# MY_FOC_2.net
KiCad netlist of a schematic drawn in Altium Designer
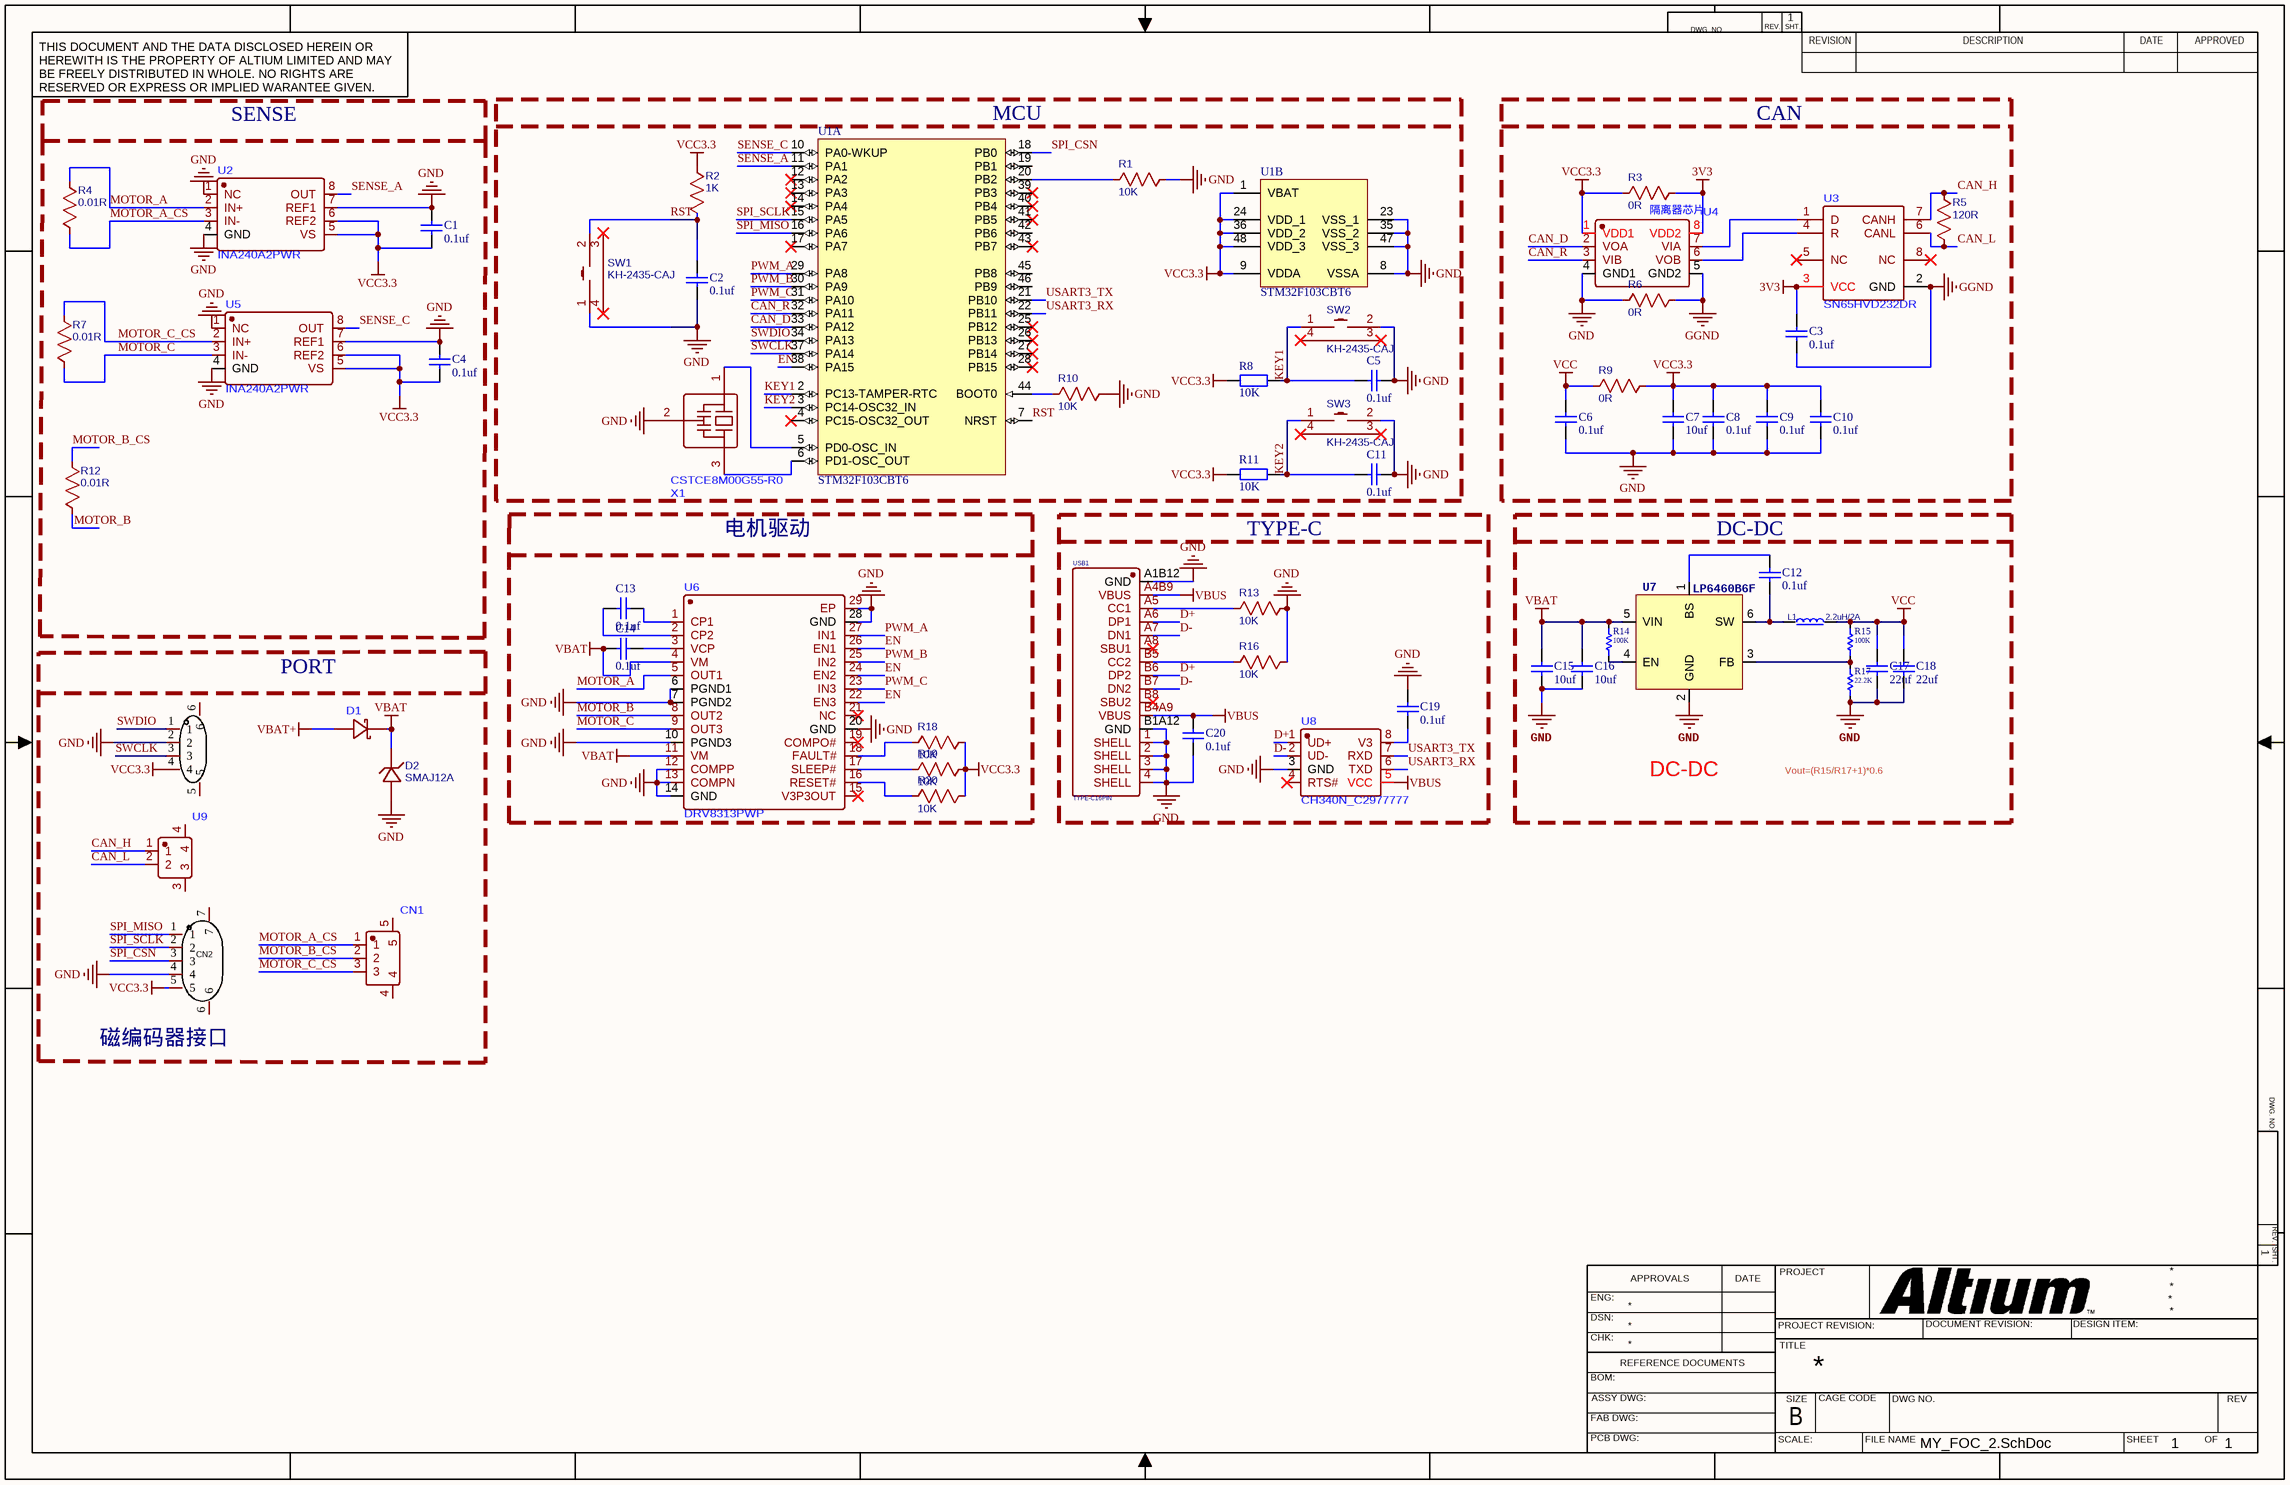
[diagram p0: MY_FOC_2.SchDoc]

(export (version "E")
  (design (tool "Eeschema 10.0.6"))
  (components
    (comp (ref "C1")
      (value "0.1uf")
      (footprint "CAP_0402")
      (description "Capacitor")
      (fields (field (name "Comment") "Cap") (field (name "PUBLISHER") "Altium Limited"))
      (libsource (lib "simple_foc") (part "Cap"))
    )
    (comp (ref "C2")
      (value "0.1uf")
      (footprint "CAP_0402")
      (description "Capacitor")
      (fields (field (name "Comment") "Cap") (field (name "PUBLISHER") "Altium Limited"))
      (libsource (lib "simple_foc") (part "Cap"))
    )
    (comp (ref "C3")
      (value "0.1uf")
      (footprint "CAP_0402")
      (description "Capacitor")
      (fields (field (name "Comment") "Cap") (field (name "PUBLISHER") "Altium Limited"))
      (libsource (lib "simple_foc") (part "Cap"))
    )
    (comp (ref "C4")
      (value "0.1uf")
      (footprint "CAP_0402")
      (description "Capacitor")
      (fields (field (name "Comment") "Cap") (field (name "PUBLISHER") "Altium Limited"))
      (libsource (lib "simple_foc") (part "Cap"))
    )
    (comp (ref "C5")
      (value "0.1uf")
      (footprint "CAP_0402")
      (description "Capacitor")
      (fields (field (name "Comment") "Cap") (field (name "PUBLISHER") "Altium Limited"))
      (libsource (lib "simple_foc") (part "Cap"))
    )
    (comp (ref "C6")
      (value "0.1uf")
      (footprint "CAP_0402")
      (description "Capacitor")
      (fields (field (name "Comment") "Cap") (field (name "PUBLISHER") "Altium Limited"))
      (libsource (lib "simple_foc") (part "Cap"))
    )
    (comp (ref "C7")
      (value "10uf")
      (footprint "CAP_0402")
      (description "Capacitor")
      (fields (field (name "Comment") "Cap") (field (name "PUBLISHER") "Altium Limited"))
      (libsource (lib "simple_foc") (part "Cap"))
    )
    (comp (ref "C8")
      (value "0.1uf")
      (footprint "CAP_0402")
      (description "Capacitor")
      (fields (field (name "Comment") "Cap") (field (name "PUBLISHER") "Altium Limited"))
      (libsource (lib "simple_foc") (part "Cap"))
    )
    (comp (ref "C9")
      (value "0.1uf")
      (footprint "CAP_0402")
      (description "Capacitor")
      (fields (field (name "Comment") "Cap") (field (name "PUBLISHER") "Altium Limited"))
      (libsource (lib "simple_foc") (part "Cap"))
    )
    (comp (ref "C10")
      (value "0.1uf")
      (footprint "CAP_0402")
      (description "Capacitor")
      (fields (field (name "Comment") "Cap") (field (name "PUBLISHER") "Altium Limited"))
      (libsource (lib "simple_foc") (part "Cap"))
    )
    (comp (ref "C11")
      (value "0.1uf")
      (footprint "CAP_0402")
      (description "Capacitor")
      (fields (field (name "Comment") "Cap") (field (name "PUBLISHER") "Altium Limited"))
      (libsource (lib "simple_foc") (part "Cap"))
    )
    (comp (ref "C12")
      (value "0.1uf")
      (footprint "CAP_0402")
      (description "Capacitor")
      (fields (field (name "Comment") "Cap") (field (name "PUBLISHER") "Altium Limited"))
      (libsource (lib "simple_foc") (part "Cap"))
    )
    (comp (ref "C13")
      (value "0.1uf")
      (footprint "CAP_0402")
      (description "Capacitor")
      (fields (field (name "Comment") "Cap") (field (name "PUBLISHER") "Altium Limited"))
      (libsource (lib "simple_foc") (part "Cap"))
    )
    (comp (ref "C14")
      (value "0.1uf")
      (footprint "CAP_0402")
      (description "Capacitor")
      (fields (field (name "Comment") "Cap") (field (name "PUBLISHER") "Altium Limited"))
      (libsource (lib "simple_foc") (part "Cap"))
    )
    (comp (ref "C15")
      (value "10uf")
      (footprint "CAP_0402")
      (description "Capacitor")
      (fields (field (name "Comment") "Cap") (field (name "PUBLISHER") "Altium Limited"))
      (libsource (lib "simple_foc") (part "Cap"))
    )
    (comp (ref "C16")
      (value "10uf")
      (footprint "CAP_0402")
      (description "Capacitor")
      (fields (field (name "Comment") "Cap") (field (name "PUBLISHER") "Altium Limited"))
      (libsource (lib "simple_foc") (part "Cap"))
    )
    (comp (ref "C17")
      (value "22uf")
      (footprint "CAP_0402")
      (description "Capacitor")
      (fields (field (name "Comment") "Cap") (field (name "PUBLISHER") "Altium Limited"))
      (libsource (lib "simple_foc") (part "Cap"))
    )
    (comp (ref "C18")
      (value "22uf")
      (footprint "CAP_0402")
      (description "Capacitor")
      (fields (field (name "Comment") "Cap") (field (name "PUBLISHER") "Altium Limited"))
      (libsource (lib "simple_foc") (part "Cap"))
    )
    (comp (ref "C19")
      (value "0.1uf")
      (footprint "CAP_0402")
      (description "Capacitor")
      (fields (field (name "Comment") "Cap") (field (name "PUBLISHER") "Altium Limited"))
      (libsource (lib "simple_foc") (part "Cap"))
    )
    (comp (ref "C20")
      (value "0.1uf")
      (footprint "CAP_0402")
      (description "Capacitor")
      (fields (field (name "Comment") "Cap") (field (name "PUBLISHER") "Altium Limited"))
      (libsource (lib "simple_foc") (part "Cap"))
    )
    (comp (ref "CN1")
      (value "~")
      (footprint "SH1.0-3P-L")
      (libsource (lib "altium-import") (part "root_0_SH1.0-3P-L_"))
    )
    (comp (ref "CN2")
      (value "HDGC1002WR-S-5P")
      (footprint "SH1.0-5P-L")
      (fields (field (name "MANUFACTURER") "HDGC(华德共创)"))
      (libsource (lib "altium-import") (part "root_0_HDGC1002WR-S-5P_"))
    )
    (comp (ref "CN3")
      (value "HDGC1002WR-S-4P")
      (footprint "SH1.0-4P-L")
      (fields (field (name "MANUFACTURER") "HDGC(华德共创)"))
      (libsource (lib "altium-import") (part "root_0_HDGC1002WR-S-4P_"))
    )
    (comp (ref "D1")
      (value "~")
      (footprint "DO-214AC - duplicate")
      (libsource (lib "altium-import") (part "root_2_SS54A_"))
    )
    (comp (ref "D2")
      (value "SMAJ12A")
      (footprint "SMA_L4.4-W2.8-LS5.4-RD")
      (fields
        (field (name "BOM_SUPPLIER PART") "C309908")
        (field (name "BOM_MANUFACTURER PART") "SMAJ70A")
        (field (name "CONTRIBUTOR") "LCSC")
      )
      (libsource (lib "Schlib1") (part "SMAJ12A"))
    )
    (comp (ref "L1")
      (value "2.2uH/2A")
      (footprint "Inductor_CD_43")
      (description "贴片电感")
      (libsource (lib "*") (part "PL4020"))
    )
    (comp (ref "R1")
      (value "10K")
      (footprint "RES_0402")
      (fields (field (name "CONTRIBUTOR") "LCEDA_Lib"))
      (libsource (lib "simple_foc") (part "0R"))
    )
    (comp (ref "R2")
      (value "1K")
      (footprint "RES_0402")
      (fields (field (name "CONTRIBUTOR") "LCEDA_Lib"))
      (libsource (lib "simple_foc") (part "0R"))
    )
    (comp (ref "R3")
      (value "0R")
      (footprint "RES_0402")
      (fields (field (name "CONTRIBUTOR") "LCEDA_Lib"))
      (libsource (lib "simple_foc") (part "0R"))
    )
    (comp (ref "R4")
      (value "0.01R")
      (footprint "R1206")
      (fields (field (name "CONTRIBUTOR") "LCEDA_Lib"))
      (libsource (lib "simple_foc") (part "0R"))
    )
    (comp (ref "R5")
      (value "120R")
      (footprint "RES_0402")
      (fields (field (name "CONTRIBUTOR") "LCEDA_Lib"))
      (libsource (lib "simple_foc") (part "0R"))
    )
    (comp (ref "R6")
      (value "0R")
      (footprint "RES_0402")
      (fields (field (name "CONTRIBUTOR") "LCEDA_Lib"))
      (libsource (lib "simple_foc") (part "0R"))
    )
    (comp (ref "R7")
      (value "0.01R")
      (footprint "R1206")
      (fields (field (name "CONTRIBUTOR") "LCEDA_Lib"))
      (libsource (lib "simple_foc") (part "0R"))
    )
    (comp (ref "R8")
      (value "10K")
      (footprint "RES_0402")
      (description "贴片电阻")
      (fields (field (name "版权归属") "来自淘宝 ID：黄晶宝石"))
      (libsource (lib "0.1 - 电阻-电容-电感") (part "R"))
    )
    (comp (ref "R9")
      (value "0R")
      (footprint "R1206")
      (fields (field (name "CONTRIBUTOR") "LCEDA_Lib"))
      (libsource (lib "simple_foc") (part "0R"))
    )
    (comp (ref "R10")
      (value "10K")
      (footprint "RES_0402")
      (fields (field (name "CONTRIBUTOR") "LCEDA_Lib"))
      (libsource (lib "simple_foc") (part "0R"))
    )
    (comp (ref "R11")
      (value "10K")
      (footprint "RES_0402")
      (description "贴片电阻")
      (fields (field (name "版权归属") "来自淘宝 ID：黄晶宝石"))
      (libsource (lib "0.1 - 电阻-电容-电感") (part "R"))
    )
    (comp (ref "R12")
      (value "0.01R")
      (footprint "R1206")
      (fields (field (name "CONTRIBUTOR") "LCEDA_Lib"))
      (libsource (lib "simple_foc") (part "0R"))
    )
    (comp (ref "R13")
      (value "10K")
      (footprint "RES_0402")
      (fields (field (name "CONTRIBUTOR") "LCEDA_Lib"))
      (libsource (lib "simple_foc") (part "0R"))
    )
    (comp (ref "R14")
      (value "100K")
      (footprint "RES_0402")
      (description "贴片电阻")
      (libsource (lib "SuperKnob") (part "电阻-0402"))
    )
    (comp (ref "R15")
      (value "100K")
      (footprint "RES_0402")
      (description "贴片电阻")
      (libsource (lib "SuperKnob") (part "电阻-0402"))
    )
    (comp (ref "R16")
      (value "10K")
      (footprint "RES_0402")
      (fields (field (name "CONTRIBUTOR") "LCEDA_Lib"))
      (libsource (lib "simple_foc") (part "0R"))
    )
    (comp (ref "R17")
      (value "22.2K")
      (footprint "RES_0402")
      (description "贴片电阻")
      (libsource (lib "SuperKnob") (part "电阻-0402"))
    )
    (comp (ref "R18")
      (value "10K")
      (footprint "RES_0402")
      (fields (field (name "CONTRIBUTOR") "LCEDA_Lib"))
      (libsource (lib "simple_foc") (part "0R"))
    )
    (comp (ref "R19")
      (value "10K")
      (footprint "RES_0402")
      (fields (field (name "CONTRIBUTOR") "LCEDA_Lib"))
      (libsource (lib "simple_foc") (part "0R"))
    )
    (comp (ref "R20")
      (value "10K")
      (footprint "RES_0402")
      (fields (field (name "CONTRIBUTOR") "LCEDA_Lib"))
      (libsource (lib "simple_foc") (part "0R"))
    )
    (comp (ref "SW1")
      (value "KH-2435-CAJ")
      (footprint "SW-SMD_KH-2435-CAJ")
      (fields
        (field (name "BOM_SUPPLIER PART") "C255808")
        (field (name "BOM_MANUFACTURER PART") "1TS003B-1600-3500A")
        (field (name "CONTRIBUTOR") "LCSC")
      )
      (libsource (lib "altium-import") (part "root_1_KH-2435-CAJ_"))
    )
    (comp (ref "SW2")
      (value "KH-2435-CAJ")
      (footprint "SW-SMD_KH-2435-CAJ")
      (fields
        (field (name "BOM_SUPPLIER PART") "C255808")
        (field (name "BOM_MANUFACTURER PART") "1TS003B-1600-3500A")
        (field (name "CONTRIBUTOR") "LCSC")
      )
      (libsource (lib "altium-import") (part "root_0_KH-2435-CAJ_"))
    )
    (comp (ref "SW3")
      (value "KH-2435-CAJ")
      (footprint "SW-SMD_KH-2435-CAJ")
      (fields
        (field (name "BOM_SUPPLIER PART") "C255808")
        (field (name "BOM_MANUFACTURER PART") "1TS003B-1600-3500A")
        (field (name "CONTRIBUTOR") "LCSC")
      )
      (libsource (lib "altium-import") (part "root_0_KH-2435-CAJ_"))
    )
    (comp (ref "U1")
      (value "STM32F103CBT6")
      (footprint "simple_foc:LQFP-48")
      (libsource (lib "STMicroelectronics STM32 F1") (part "STM32F103CBT6"))
    )
    (comp (ref "U2")
      (value "INA240A2PWR")
      (footprint "TSSOP-8_L4.4-W3.0-P0.65-LS6.4-BL")
      (libsource (lib "simple_foc") (part "INA240A2PWR"))
    )
    (comp (ref "U3")
      (value "SN65HVD232DR")
      (footprint "SOIC-8_L5.0-W4.0-P1.27-LS6.0-BL")
      (libsource (lib "simple_foc") (part "SN65HVD232DR"))
    )
    (comp (ref "U4")
      (value "隔离器芯片")
      (footprint "SOIC-8_L4.9-W3.9-P1.27-LS6.0-BL")
      (libsource (lib "altium-import") (part "root_0_[JLCSMT]-ADUM1201ARZ-RL7_"))
    )
    (comp (ref "U5")
      (value "INA240A2PWR")
      (footprint "TSSOP-8_L4.4-W3.0-P0.65-LS6.4-BL")
      (libsource (lib "simple_foc") (part "INA240A2PWR"))
    )
    (comp (ref "U6")
      (value "DRV8313PWP")
      (footprint "HTSSOP-28_L9.8-W4.5-P0.65-LS6.6-BL-EP")
      (libsource (lib "simple_foc") (part "DRV8313PWP"))
    )
    (comp (ref "U7")
      (value "LP6460B6F")
      (footprint "SOT23_6")
      (description "DC-DC芯片")
      (libsource (lib "SuperKnob") (part "LP6460B6F"))
    )
    (comp (ref "U8")
      (value "CH340N_C2977777")
      (footprint "SOP-8_L4.9-W3.9-P1.27-LS6.0-BL")
      (libsource (lib "simple_foc") (part "CH340N_C2977777"))
    )
    (comp (ref "U9")
      (value "~")
      (footprint "SH1.0-2P-L")
      (libsource (lib "altium-import") (part "root_0_WAFER-SH1.0-2PWB_"))
    )
    (comp (ref "USB1")
      (value "TYPE-C16PIN")
      (footprint "USB-C-SMD_TYPE-C16PIN")
      (fields (field (name "BOM_SUPPLIER PART") "C393939") (field (name "CONTRIBUTOR") "LCSC"))
      (libsource (lib "simple_foc") (part "TYPE-C16PIN"))
    )
    (comp (ref "X1")
      (value "CSTCE8M00G55-R0")
      (footprint "OSC-SMD_3P-L3.2-W1.3-P1.2-L")
      (libsource (lib "simple_foc") (part "CSTCE8M00G55-R0"))
    )
  )
  (nets
    (net (code "2") (name "/CAN_D") (class "Default")
      (node (ref "U1") (pin "33") (pinfunction "PA12_33") (pintype "bidirectional"))
      (node (ref "U4") (pin "2") (pinfunction "VOA_2") (pintype "passive"))
    )
    (net (code "3") (name "/CAN_H") (class "Default")
      (node (ref "R5") (pin "1") (pinfunction "1_1") (pintype "passive"))
      (node (ref "U3") (pin "7") (pinfunction "CANH_7") (pintype "passive"))
      (node (ref "U9") (pin "1") (pinfunction "1_1") (pintype "passive"))
    )
    (net (code "4") (name "/CAN_L") (class "Default")
      (node (ref "R5") (pin "2") (pinfunction "2_2") (pintype "passive"))
      (node (ref "U3") (pin "6") (pinfunction "CANL_6") (pintype "passive"))
      (node (ref "U9") (pin "2") (pinfunction "2_2") (pintype "passive"))
    )
    (net (code "5") (name "/CAN_R") (class "Default")
      (node (ref "U1") (pin "32") (pinfunction "PA11_32") (pintype "bidirectional"))
      (node (ref "U4") (pin "3") (pinfunction "VIB_3") (pintype "passive"))
    )
    (net (code "6") (name "/D+") (class "Default")
      (node (ref "U8") (pin "1") (pinfunction "UD+_1") (pintype "passive"))
      (node (ref "USB1") (pin "A6") (pinfunction "DP1_A6") (pintype "passive"))
      (node (ref "USB1") (pin "B6") (pinfunction "DP2_B6") (pintype "passive"))
    )
    (net (code "7") (name "/D-") (class "Default")
      (node (ref "U8") (pin "2") (pinfunction "UD-_2") (pintype "passive"))
      (node (ref "USB1") (pin "A7") (pinfunction "DN1_A7") (pintype "passive"))
      (node (ref "USB1") (pin "B7") (pinfunction "DN2_B7") (pintype "passive"))
    )
    (net (code "8") (name "/EN") (class "Default")
      (node (ref "U1") (pin "38") (pinfunction "PA15_38") (pintype "bidirectional"))
      (node (ref "U6") (pin "22") (pinfunction "EN3_22") (pintype "passive"))
      (node (ref "U6") (pin "24") (pinfunction "EN2_24") (pintype "passive"))
      (node (ref "U6") (pin "26") (pinfunction "EN1_26") (pintype "passive"))
    )
    (net (code "9") (name "/KEY1") (class "Default")
      (node (ref "C5") (pin "2") (pinfunction "2_2") (pintype "passive"))
      (node (ref "R8") (pin "2") (pinfunction "2_2") (pintype "passive"))
      (node (ref "SW2") (pin "1") (pinfunction "1_1") (pintype "passive"))
      (node (ref "U1") (pin "2") (pinfunction "PC13-TAMPER-RTC_2") (pintype "bidirectional"))
    )
    (net (code "10") (name "/KEY2") (class "Default")
      (node (ref "C11") (pin "2") (pinfunction "2_2") (pintype "passive"))
      (node (ref "R11") (pin "2") (pinfunction "2_2") (pintype "passive"))
      (node (ref "SW3") (pin "1") (pinfunction "1_1") (pintype "passive"))
      (node (ref "U1") (pin "3") (pinfunction "PC14-OSC32_IN_3") (pintype "bidirectional"))
    )
    (net (code "11") (name "/MOTOR_A") (class "Default")
      (node (ref "R4") (pin "2") (pinfunction "2_2") (pintype "passive"))
      (node (ref "U2") (pin "2") (pinfunction "IN+_2") (pintype "passive"))
      (node (ref "U6") (pin "5") (pinfunction "OUT1_5") (pintype "passive"))
    )
    (net (code "12") (name "/MOTOR_A_CS") (class "Default")
      (node (ref "CN1") (pin "1") (pinfunction "1_1") (pintype "passive"))
      (node (ref "R4") (pin "1") (pinfunction "1_1") (pintype "passive"))
      (node (ref "U2") (pin "3") (pinfunction "IN-_3") (pintype "passive"))
    )
    (net (code "13") (name "/MOTOR_B") (class "Default")
      (node (ref "R12") (pin "1") (pinfunction "1_1") (pintype "passive"))
      (node (ref "U6") (pin "8") (pinfunction "OUT2_8") (pintype "passive"))
    )
    (net (code "14") (name "/MOTOR_B_CS") (class "Default")
      (node (ref "CN1") (pin "2") (pinfunction "2_2") (pintype "passive"))
      (node (ref "R12") (pin "2") (pinfunction "2_2") (pintype "passive"))
    )
    (net (code "15") (name "/MOTOR_C") (class "Default")
      (node (ref "R7") (pin "1") (pinfunction "1_1") (pintype "passive"))
      (node (ref "U5") (pin "3") (pinfunction "IN-_3") (pintype "passive"))
      (node (ref "U6") (pin "9") (pinfunction "OUT3_9") (pintype "passive"))
    )
    (net (code "16") (name "/MOTOR_C_CS") (class "Default")
      (node (ref "CN1") (pin "3") (pinfunction "3_3") (pintype "passive"))
      (node (ref "R7") (pin "2") (pinfunction "2_2") (pintype "passive"))
      (node (ref "U5") (pin "2") (pinfunction "IN+_2") (pintype "passive"))
    )
    (net (code "17") (name "/PWM_A") (class "Default")
      (node (ref "U1") (pin "29") (pinfunction "PA8_29") (pintype "bidirectional"))
      (node (ref "U6") (pin "27") (pinfunction "IN1_27") (pintype "passive"))
    )
    (net (code "18") (name "/PWM_B") (class "Default")
      (node (ref "U1") (pin "30") (pinfunction "PA9_30") (pintype "bidirectional"))
      (node (ref "U6") (pin "25") (pinfunction "IN2_25") (pintype "passive"))
    )
    (net (code "19") (name "/PWM_C") (class "Default")
      (node (ref "U1") (pin "31") (pinfunction "PA10_31") (pintype "bidirectional"))
      (node (ref "U6") (pin "23") (pinfunction "IN3_23") (pintype "passive"))
    )
    (net (code "20") (name "/RST") (class "Default")
      (node (ref "C2") (pin "2") (pinfunction "2_2") (pintype "passive"))
      (node (ref "R2") (pin "2") (pinfunction "2_2") (pintype "passive"))
      (node (ref "SW1") (pin "2") (pinfunction "2_2") (pintype "passive"))
      (node (ref "U1") (pin "7") (pinfunction "NRST_7") (pintype "bidirectional"))
    )
    (net (code "21") (name "/SENSE_A") (class "Default")
      (node (ref "U1") (pin "11") (pinfunction "PA1_11") (pintype "bidirectional"))
      (node (ref "U2") (pin "8") (pinfunction "OUT_8") (pintype "passive"))
    )
    (net (code "22") (name "/SENSE_C") (class "Default")
      (node (ref "U1") (pin "10") (pinfunction "PA0-WKUP_10") (pintype "bidirectional"))
      (node (ref "U5") (pin "8") (pinfunction "OUT_8") (pintype "passive"))
    )
    (net (code "23") (name "/SPI_CSN") (class "Default")
      (node (ref "CN2") (pin "3") (pinfunction "3_3") (pintype "passive"))
      (node (ref "U1") (pin "18") (pinfunction "PB0_18") (pintype "bidirectional"))
    )
    (net (code "24") (name "/SPI_MISO") (class "Default")
      (node (ref "CN2") (pin "1") (pinfunction "1_1") (pintype "passive"))
      (node (ref "U1") (pin "16") (pinfunction "PA6_16") (pintype "bidirectional"))
    )
    (net (code "25") (name "/SPI_SCLK") (class "Default")
      (node (ref "CN2") (pin "2") (pinfunction "2_2") (pintype "passive"))
      (node (ref "U1") (pin "15") (pinfunction "PA5_15") (pintype "bidirectional"))
    )
    (net (code "26") (name "/SWCLK") (class "Default")
      (node (ref "CN3") (pin "3") (pinfunction "3_3") (pintype "passive"))
      (node (ref "U1") (pin "37") (pinfunction "PA14_37") (pintype "bidirectional"))
    )
    (net (code "27") (name "/SWDIO") (class "Default")
      (node (ref "CN3") (pin "1") (pinfunction "1_1") (pintype "passive"))
      (node (ref "U1") (pin "34") (pinfunction "PA13_34") (pintype "bidirectional"))
    )
    (net (code "28") (name "/USART3_RX") (class "Default")
      (node (ref "U1") (pin "22") (pinfunction "PB11_22") (pintype "bidirectional"))
      (node (ref "U8") (pin "6") (pinfunction "TXD_6") (pintype "passive"))
    )
    (net (code "29") (name "/USART3_TX") (class "Default")
      (node (ref "U1") (pin "21") (pinfunction "PB10_21") (pintype "bidirectional"))
      (node (ref "U8") (pin "7") (pinfunction "RXD_7") (pintype "passive"))
    )
    (net (code "30") (name "3V3") (class "Default")
      (node (ref "C3") (pin "2") (pinfunction "2_2") (pintype "passive"))
      (node (ref "R3") (pin "2") (pinfunction "2_2") (pintype "passive"))
      (node (ref "U3") (pin "3") (pinfunction "VCC_3") (pintype "passive"))
      (node (ref "U4") (pin "8") (pinfunction "VDD2_8") (pintype "passive"))
    )
    (net (code "31") (name "GGND") (class "Default")
      (node (ref "C3") (pin "1") (pinfunction "1_1") (pintype "passive"))
      (node (ref "R6") (pin "2") (pinfunction "2_2") (pintype "passive"))
      (node (ref "U3") (pin "2") (pinfunction "GND_2") (pintype "passive"))
      (node (ref "U4") (pin "5") (pinfunction "GND2_5") (pintype "passive"))
    )
    (net (code "32") (name "GND") (class "Default")
      (node (ref "C1") (pin "2") (pinfunction "2_2") (pintype "passive"))
      (node (ref "C10") (pin "1") (pinfunction "1_1") (pintype "passive"))
      (node (ref "C11") (pin "1") (pinfunction "1_1") (pintype "passive"))
      (node (ref "C15") (pin "2") (pinfunction "2_2") (pintype "passive"))
      (node (ref "C16") (pin "2") (pinfunction "2_2") (pintype "passive"))
      (node (ref "C17") (pin "2") (pinfunction "2_2") (pintype "passive"))
      (node (ref "C18") (pin "2") (pinfunction "2_2") (pintype "passive"))
      (node (ref "C19") (pin "1") (pinfunction "1_1") (pintype "passive"))
      (node (ref "C2") (pin "1") (pinfunction "1_1") (pintype "passive"))
      (node (ref "C20") (pin "2") (pinfunction "2_2") (pintype "passive"))
      (node (ref "C4") (pin "2") (pinfunction "2_2") (pintype "passive"))
      (node (ref "C5") (pin "1") (pinfunction "1_1") (pintype "passive"))
      (node (ref "C6") (pin "1") (pinfunction "1_1") (pintype "passive"))
      (node (ref "C7") (pin "1") (pinfunction "1_1") (pintype "passive"))
      (node (ref "C8") (pin "1") (pinfunction "1_1") (pintype "passive"))
      (node (ref "C9") (pin "1") (pinfunction "1_1") (pintype "passive"))
      (node (ref "CN2") (pin "4") (pinfunction "4_4") (pintype "passive"))
      (node (ref "CN3") (pin "2") (pinfunction "2_2") (pintype "passive"))
      (node (ref "D2") (pin "2") (pinfunction "2_2") (pintype "passive"))
      (node (ref "R1") (pin "1") (pinfunction "1_1") (pintype "passive"))
      (node (ref "R10") (pin "1") (pinfunction "1_1") (pintype "passive"))
      (node (ref "R13") (pin "1") (pinfunction "1_1") (pintype "passive"))
      (node (ref "R16") (pin "1") (pinfunction "1_1") (pintype "passive"))
      (node (ref "R17") (pin "2") (pinfunction "2_2") (pintype "passive"))
      (node (ref "R6") (pin "1") (pinfunction "1_1") (pintype "passive"))
      (node (ref "SW1") (pin "1") (pinfunction "1_1") (pintype "passive"))
      (node (ref "SW2") (pin "2") (pinfunction "2_2") (pintype "passive"))
      (node (ref "SW3") (pin "2") (pinfunction "2_2") (pintype "passive"))
      (node (ref "U1") (pin "23") (pinfunction "VSS_1_23") (pintype "power_in"))
      (node (ref "U1") (pin "35") (pinfunction "VSS_2_35") (pintype "power_in"))
      (node (ref "U1") (pin "47") (pinfunction "VSS_3_47") (pintype "power_in"))
      (node (ref "U1") (pin "8") (pinfunction "VSSA_8") (pintype "power_in"))
      (node (ref "U2") (pin "1") (pinfunction "NC_1") (pintype "passive"))
      (node (ref "U2") (pin "4") (pinfunction "GND_4") (pintype "passive"))
      (node (ref "U2") (pin "7") (pinfunction "REF1_7") (pintype "passive"))
      (node (ref "U4") (pin "4") (pinfunction "GND1_4") (pintype "passive"))
      (node (ref "U5") (pin "1") (pinfunction "NC_1") (pintype "passive"))
      (node (ref "U5") (pin "4") (pinfunction "GND_4") (pintype "passive"))
      (node (ref "U5") (pin "7") (pinfunction "REF1_7") (pintype "passive"))
      (node (ref "U6") (pin "10") (pinfunction "PGND3_10") (pintype "passive"))
      (node (ref "U6") (pin "12") (pinfunction "COMPP_12") (pintype "passive"))
      (node (ref "U6") (pin "13") (pinfunction "COMPN_13") (pintype "passive"))
      (node (ref "U6") (pin "14") (pinfunction "GND_14") (pintype "passive"))
      (node (ref "U6") (pin "20") (pinfunction "GND_20") (pintype "passive"))
      (node (ref "U6") (pin "28") (pinfunction "GND_28") (pintype "passive"))
      (node (ref "U6") (pin "29") (pinfunction "EP_29") (pintype "passive"))
      (node (ref "U6") (pin "6") (pinfunction "PGND1_6") (pintype "passive"))
      (node (ref "U6") (pin "7") (pinfunction "PGND2_7") (pintype "passive"))
      (node (ref "U7") (pin "2") (pinfunction "GND_2") (pintype "passive"))
      (node (ref "U8") (pin "3") (pinfunction "GND_3") (pintype "passive"))
      (node (ref "USB1") (pin "1") (pinfunction "SHELL_1") (pintype "passive"))
      (node (ref "USB1") (pin "2") (pinfunction "SHELL_2") (pintype "passive"))
      (node (ref "USB1") (pin "3") (pinfunction "SHELL_3") (pintype "passive"))
      (node (ref "USB1") (pin "4") (pinfunction "SHELL_4") (pintype "passive"))
      (node (ref "USB1") (pin "A1B12") (pinfunction "GND_A1B12") (pintype "passive"))
      (node (ref "USB1") (pin "B1A12") (pinfunction "GND_B1A12") (pintype "passive"))
      (node (ref "X1") (pin "2") (pinfunction "VSS_2") (pintype "passive"))
    )
    (net (code "33") (name "Net-(U1A-BOOT0)") (class "Default")
      (node (ref "R10") (pin "2") (pinfunction "2_2") (pintype "passive"))
      (node (ref "U1") (pin "44") (pinfunction "BOOT0_44") (pintype "input"))
    )
    (net (code "34") (name "Net-(U1A-PB2)") (class "Default")
      (node (ref "R1") (pin "2") (pinfunction "2_2") (pintype "passive"))
      (node (ref "U1") (pin "20") (pinfunction "PB2_20") (pintype "bidirectional"))
    )
    (net (code "35") (name "Net-(U1A-PD0-OSC_IN)") (class "Default")
      (node (ref "U1") (pin "5") (pinfunction "PD0-OSC_IN_5") (pintype "bidirectional"))
      (node (ref "X1") (pin "1") (pinfunction "1_1") (pintype "passive"))
    )
    (net (code "36") (name "Net-(U1A-PD1-OSC_OUT)") (class "Default")
      (node (ref "U1") (pin "6") (pinfunction "PD1-OSC_OUT_6") (pintype "bidirectional"))
      (node (ref "X1") (pin "3") (pinfunction "3_3") (pintype "passive"))
    )
    (net (code "37") (name "Net-(U3-D)") (class "Default")
      (node (ref "U3") (pin "1") (pinfunction "D_1") (pintype "passive"))
      (node (ref "U4") (pin "7") (pinfunction "VIA_7") (pintype "passive"))
    )
    (net (code "38") (name "Net-(U3-R)") (class "Default")
      (node (ref "U3") (pin "4") (pinfunction "R_4") (pintype "passive"))
      (node (ref "U4") (pin "6") (pinfunction "VOB_6") (pintype "passive"))
    )
    (net (code "39") (name "Net-(U6-CP1)") (class "Default")
      (node (ref "C13") (pin "1") (pinfunction "1_1") (pintype "passive"))
      (node (ref "U6") (pin "1") (pinfunction "CP1_1") (pintype "passive"))
    )
    (net (code "40") (name "Net-(U6-CP2)") (class "Default")
      (node (ref "C13") (pin "2") (pinfunction "2_2") (pintype "passive"))
      (node (ref "U6") (pin "2") (pinfunction "CP2_2") (pintype "passive"))
    )
    (net (code "41") (name "Net-(U6-FAULT#)") (class "Default")
      (node (ref "R18") (pin "2") (pinfunction "2_2") (pintype "passive"))
      (node (ref "U6") (pin "18") (pinfunction "FAULT#_18") (pintype "passive"))
    )
    (net (code "42") (name "Net-(U6-RESET#)") (class "Default")
      (node (ref "R20") (pin "2") (pinfunction "2_2") (pintype "passive"))
      (node (ref "U6") (pin "16") (pinfunction "RESET#_16") (pintype "passive"))
    )
    (net (code "43") (name "Net-(U6-SLEEP#)") (class "Default")
      (node (ref "R19") (pin "2") (pinfunction "2_2") (pintype "passive"))
      (node (ref "U6") (pin "17") (pinfunction "SLEEP#_17") (pintype "passive"))
    )
    (net (code "44") (name "Net-(U6-VCP)") (class "Default")
      (node (ref "C14") (pin "1") (pinfunction "1_1") (pintype "passive"))
      (node (ref "U6") (pin "3") (pinfunction "VCP_3") (pintype "passive"))
    )
    (net (code "45") (name "Net-(U7-BS)") (class "Default")
      (node (ref "C12") (pin "1") (pinfunction "1_1") (pintype "passive"))
      (node (ref "U7") (pin "1") (pinfunction "BS_1") (pintype "passive"))
    )
    (net (code "46") (name "Net-(U7-EN)") (class "Default")
      (node (ref "R14") (pin "2") (pinfunction "2_2") (pintype "passive"))
      (node (ref "U7") (pin "4") (pinfunction "EN_4") (pintype "passive"))
    )
    (net (code "47") (name "Net-(U7-FB)") (class "Default")
      (node (ref "R15") (pin "2") (pinfunction "2_2") (pintype "passive"))
      (node (ref "R17") (pin "1") (pinfunction "1_1") (pintype "passive"))
      (node (ref "U7") (pin "3") (pinfunction "FB_3") (pintype "passive"))
    )
    (net (code "48") (name "Net-(U7-SW)") (class "Default")
      (node (ref "C12") (pin "2") (pinfunction "2_2") (pintype "passive"))
      (node (ref "L1") (pin "2") (pinfunction "2_2") (pintype "passive"))
      (node (ref "U7") (pin "6") (pinfunction "SW_6") (pintype "passive"))
    )
    (net (code "49") (name "Net-(U8-V3)") (class "Default")
      (node (ref "C19") (pin "2") (pinfunction "2_2") (pintype "passive"))
      (node (ref "U8") (pin "8") (pinfunction "V3_8") (pintype "passive"))
    )
    (net (code "50") (name "Net-(USB1-CC1)") (class "Default")
      (node (ref "R13") (pin "2") (pinfunction "2_2") (pintype "passive"))
      (node (ref "USB1") (pin "A5") (pinfunction "CC1_A5") (pintype "passive"))
    )
    (net (code "51") (name "Net-(USB1-CC2)") (class "Default")
      (node (ref "R16") (pin "2") (pinfunction "2_2") (pintype "passive"))
      (node (ref "USB1") (pin "B5") (pinfunction "CC2_B5") (pintype "passive"))
    )
    (net (code "52") (name "VBAT") (class "Default")
      (node (ref "C14") (pin "2") (pinfunction "2_2") (pintype "passive"))
      (node (ref "C15") (pin "1") (pinfunction "1_1") (pintype "passive"))
      (node (ref "C16") (pin "1") (pinfunction "1_1") (pintype "passive"))
      (node (ref "D1") (pin "1") (pinfunction "C_1") (pintype "passive"))
      (node (ref "D2") (pin "1") (pinfunction "1_1") (pintype "passive"))
      (node (ref "R14") (pin "1") (pinfunction "1_1") (pintype "passive"))
      (node (ref "U6") (pin "11") (pinfunction "VM_11") (pintype "passive"))
      (node (ref "U6") (pin "4") (pinfunction "VM_4") (pintype "passive"))
      (node (ref "U7") (pin "5") (pinfunction "VIN_5") (pintype "passive"))
    )
    (net (code "53") (name "VBAT+") (class "Default")
      (node (ref "D1") (pin "2") (pinfunction "A_2") (pintype "passive"))
    )
    (net (code "54") (name "VBUS") (class "Default")
      (node (ref "C20") (pin "1") (pinfunction "1_1") (pintype "passive"))
      (node (ref "U8") (pin "5") (pinfunction "VCC_5") (pintype "passive"))
      (node (ref "USB1") (pin "A4B9") (pinfunction "VBUS_A4B9") (pintype "passive"))
      (node (ref "USB1") (pin "B4A9") (pinfunction "VBUS_B4A9") (pintype "passive"))
    )
    (net (code "55") (name "VCC") (class "Default")
      (node (ref "C17") (pin "1") (pinfunction "1_1") (pintype "passive"))
      (node (ref "C18") (pin "1") (pinfunction "1_1") (pintype "passive"))
      (node (ref "C6") (pin "2") (pinfunction "2_2") (pintype "passive"))
      (node (ref "L1") (pin "1") (pinfunction "1_1") (pintype "passive"))
      (node (ref "R15") (pin "1") (pinfunction "1_1") (pintype "passive"))
      (node (ref "R9") (pin "1") (pinfunction "1_1") (pintype "passive"))
    )
    (net (code "56") (name "VCC3.3") (class "Default")
      (node (ref "C1") (pin "1") (pinfunction "1_1") (pintype "passive"))
      (node (ref "C10") (pin "2") (pinfunction "2_2") (pintype "passive"))
      (node (ref "C4") (pin "1") (pinfunction "1_1") (pintype "passive"))
      (node (ref "C7") (pin "2") (pinfunction "2_2") (pintype "passive"))
      (node (ref "C8") (pin "2") (pinfunction "2_2") (pintype "passive"))
      (node (ref "C9") (pin "2") (pinfunction "2_2") (pintype "passive"))
      (node (ref "CN2") (pin "5") (pinfunction "5_5") (pintype "passive"))
      (node (ref "CN3") (pin "4") (pinfunction "4_4") (pintype "passive"))
      (node (ref "R11") (pin "1") (pinfunction "1_1") (pintype "passive"))
      (node (ref "R18") (pin "1") (pinfunction "1_1") (pintype "passive"))
      (node (ref "R19") (pin "1") (pinfunction "1_1") (pintype "passive"))
      (node (ref "R2") (pin "1") (pinfunction "1_1") (pintype "passive"))
      (node (ref "R20") (pin "1") (pinfunction "1_1") (pintype "passive"))
      (node (ref "R3") (pin "1") (pinfunction "1_1") (pintype "passive"))
      (node (ref "R8") (pin "1") (pinfunction "1_1") (pintype "passive"))
      (node (ref "R9") (pin "2") (pinfunction "2_2") (pintype "passive"))
      (node (ref "U1") (pin "1") (pinfunction "VBAT_1") (pintype "power_in"))
      (node (ref "U1") (pin "24") (pinfunction "VDD_1_24") (pintype "power_in"))
      (node (ref "U1") (pin "36") (pinfunction "VDD_2_36") (pintype "power_in"))
      (node (ref "U1") (pin "48") (pinfunction "VDD_3_48") (pintype "power_in"))
      (node (ref "U1") (pin "9") (pinfunction "VDDA_9") (pintype "power_in"))
      (node (ref "U2") (pin "5") (pinfunction "VS_5") (pintype "passive"))
      (node (ref "U2") (pin "6") (pinfunction "REF2_6") (pintype "passive"))
      (node (ref "U4") (pin "1") (pinfunction "VDD1_1") (pintype "passive"))
      (node (ref "U5") (pin "5") (pinfunction "VS_5") (pintype "passive"))
      (node (ref "U5") (pin "6") (pinfunction "REF2_6") (pintype "passive"))
    )
    (net (code "57") (name "unconnected-(CN1-Pad4)") (class "Default")
      (node (ref "CN1") (pin "4") (pinfunction "4_4") (pintype "passive"))
    )
    (net (code "58") (name "unconnected-(CN1-Pad5)") (class "Default")
      (node (ref "CN1") (pin "5") (pinfunction "5_5") (pintype "passive"))
    )
    (net (code "59") (name "unconnected-(CN2-Pad6)") (class "Default")
      (node (ref "CN2") (pin "6") (pinfunction "6_6") (pintype "passive"))
    )
    (net (code "60") (name "unconnected-(CN2-Pad7)") (class "Default")
      (node (ref "CN2") (pin "7") (pinfunction "7_7") (pintype "passive"))
    )
    (net (code "61") (name "unconnected-(CN3-Pad5)") (class "Default")
      (node (ref "CN3") (pin "5") (pinfunction "5_5") (pintype "passive"))
    )
    (net (code "62") (name "unconnected-(CN3-Pad6)") (class "Default")
      (node (ref "CN3") (pin "6") (pinfunction "6_6") (pintype "passive"))
    )
    (net (code "63") (name "unconnected-(SW1-Pad3)") (class "Default")
      (node (ref "SW1") (pin "3") (pinfunction "3_3") (pintype "passive+no_connect"))
    )
    (net (code "64") (name "unconnected-(SW1-Pad4)") (class "Default")
      (node (ref "SW1") (pin "4") (pinfunction "4_4") (pintype "passive+no_connect"))
    )
    (net (code "65") (name "unconnected-(SW2-Pad3)") (class "Default")
      (node (ref "SW2") (pin "3") (pinfunction "3_3") (pintype "passive+no_connect"))
    )
    (net (code "66") (name "unconnected-(SW2-Pad4)") (class "Default")
      (node (ref "SW2") (pin "4") (pinfunction "4_4") (pintype "passive+no_connect"))
    )
    (net (code "67") (name "unconnected-(SW3-Pad3)") (class "Default")
      (node (ref "SW3") (pin "3") (pinfunction "3_3") (pintype "passive+no_connect"))
    )
    (net (code "68") (name "unconnected-(SW3-Pad4)") (class "Default")
      (node (ref "SW3") (pin "4") (pinfunction "4_4") (pintype "passive+no_connect"))
    )
    (net (code "69") (name "unconnected-(U1A-PA2-Pad12)") (class "Default")
      (node (ref "U1") (pin "12") (pinfunction "PA2_12") (pintype "bidirectional+no_connect"))
    )
    (net (code "70") (name "unconnected-(U1A-PA3-Pad13)") (class "Default")
      (node (ref "U1") (pin "13") (pinfunction "PA3_13") (pintype "bidirectional+no_connect"))
    )
    (net (code "71") (name "unconnected-(U1A-PA4-Pad14)") (class "Default")
      (node (ref "U1") (pin "14") (pinfunction "PA4_14") (pintype "bidirectional+no_connect"))
    )
    (net (code "72") (name "unconnected-(U1A-PA7-Pad17)") (class "Default")
      (node (ref "U1") (pin "17") (pinfunction "PA7_17") (pintype "bidirectional+no_connect"))
    )
    (net (code "73") (name "unconnected-(U1A-PB1-Pad19)") (class "Default")
      (node (ref "U1") (pin "19") (pinfunction "PB1_19") (pintype "bidirectional"))
    )
    (net (code "74") (name "unconnected-(U1A-PB3-Pad39)") (class "Default")
      (node (ref "U1") (pin "39") (pinfunction "PB3_39") (pintype "bidirectional+no_connect"))
    )
    (net (code "75") (name "unconnected-(U1A-PB4-Pad40)") (class "Default")
      (node (ref "U1") (pin "40") (pinfunction "PB4_40") (pintype "bidirectional+no_connect"))
    )
    (net (code "76") (name "unconnected-(U1A-PB5-Pad41)") (class "Default")
      (node (ref "U1") (pin "41") (pinfunction "PB5_41") (pintype "bidirectional+no_connect"))
    )
    (net (code "77") (name "unconnected-(U1A-PB6-Pad42)") (class "Default")
      (node (ref "U1") (pin "42") (pinfunction "PB6_42") (pintype "bidirectional"))
    )
    (net (code "78") (name "unconnected-(U1A-PB7-Pad43)") (class "Default")
      (node (ref "U1") (pin "43") (pinfunction "PB7_43") (pintype "bidirectional+no_connect"))
    )
    (net (code "79") (name "unconnected-(U1A-PB8-Pad45)") (class "Default")
      (node (ref "U1") (pin "45") (pinfunction "PB8_45") (pintype "bidirectional"))
    )
    (net (code "80") (name "unconnected-(U1A-PB9-Pad46)") (class "Default")
      (node (ref "U1") (pin "46") (pinfunction "PB9_46") (pintype "bidirectional"))
    )
    (net (code "81") (name "unconnected-(U1A-PB12-Pad25)") (class "Default")
      (node (ref "U1") (pin "25") (pinfunction "PB12_25") (pintype "bidirectional+no_connect"))
    )
    (net (code "82") (name "unconnected-(U1A-PB13-Pad26)") (class "Default")
      (node (ref "U1") (pin "26") (pinfunction "PB13_26") (pintype "bidirectional+no_connect"))
    )
    (net (code "83") (name "unconnected-(U1A-PB14-Pad27)") (class "Default")
      (node (ref "U1") (pin "27") (pinfunction "PB14_27") (pintype "bidirectional+no_connect"))
    )
    (net (code "84") (name "unconnected-(U1A-PB15-Pad28)") (class "Default")
      (node (ref "U1") (pin "28") (pinfunction "PB15_28") (pintype "bidirectional+no_connect"))
    )
    (net (code "85") (name "unconnected-(U1A-PC15-OSC32_OUT-Pad4)") (class "Default")
      (node (ref "U1") (pin "4") (pinfunction "PC15-OSC32_OUT_4") (pintype "bidirectional+no_connect"))
    )
    (net (code "86") (name "unconnected-(U3-NC-Pad5)") (class "Default")
      (node (ref "U3") (pin "5") (pinfunction "NC_5") (pintype "passive+no_connect"))
    )
    (net (code "87") (name "unconnected-(U3-NC-Pad8)") (class "Default")
      (node (ref "U3") (pin "8") (pinfunction "NC_8") (pintype "passive+no_connect"))
    )
    (net (code "88") (name "unconnected-(U6-COMPO#-Pad19)") (class "Default")
      (node (ref "U6") (pin "19") (pinfunction "COMPO#_19") (pintype "passive+no_connect"))
    )
    (net (code "89") (name "unconnected-(U6-NC-Pad21)") (class "Default")
      (node (ref "U6") (pin "21") (pinfunction "NC_21") (pintype "passive+no_connect"))
    )
    (net (code "90") (name "unconnected-(U6-V3P3OUT-Pad15)") (class "Default")
      (node (ref "U6") (pin "15") (pinfunction "V3P3OUT_15") (pintype "passive+no_connect"))
    )
    (net (code "91") (name "unconnected-(U8-RTS#-Pad4)") (class "Default")
      (node (ref "U8") (pin "4") (pinfunction "RTS#_4") (pintype "passive+no_connect"))
    )
    (net (code "92") (name "unconnected-(U9-Pad3)") (class "Default")
      (node (ref "U9") (pin "3") (pinfunction "3_3") (pintype "passive"))
    )
    (net (code "93") (name "unconnected-(U9-Pad4)") (class "Default")
      (node (ref "U9") (pin "4") (pinfunction "4_4") (pintype "passive"))
    )
    (net (code "94") (name "unconnected-(USB1-SBU1-PadA8)") (class "Default")
      (node (ref "USB1") (pin "A8") (pinfunction "SBU1_A8") (pintype "passive+no_connect"))
    )
    (net (code "95") (name "unconnected-(USB1-SBU2-PadB8)") (class "Default")
      (node (ref "USB1") (pin "B8") (pinfunction "SBU2_B8") (pintype "passive+no_connect"))
    )
  )
)
